# Main.net
KiCad netlist of a schematic drawn in Altium Designer
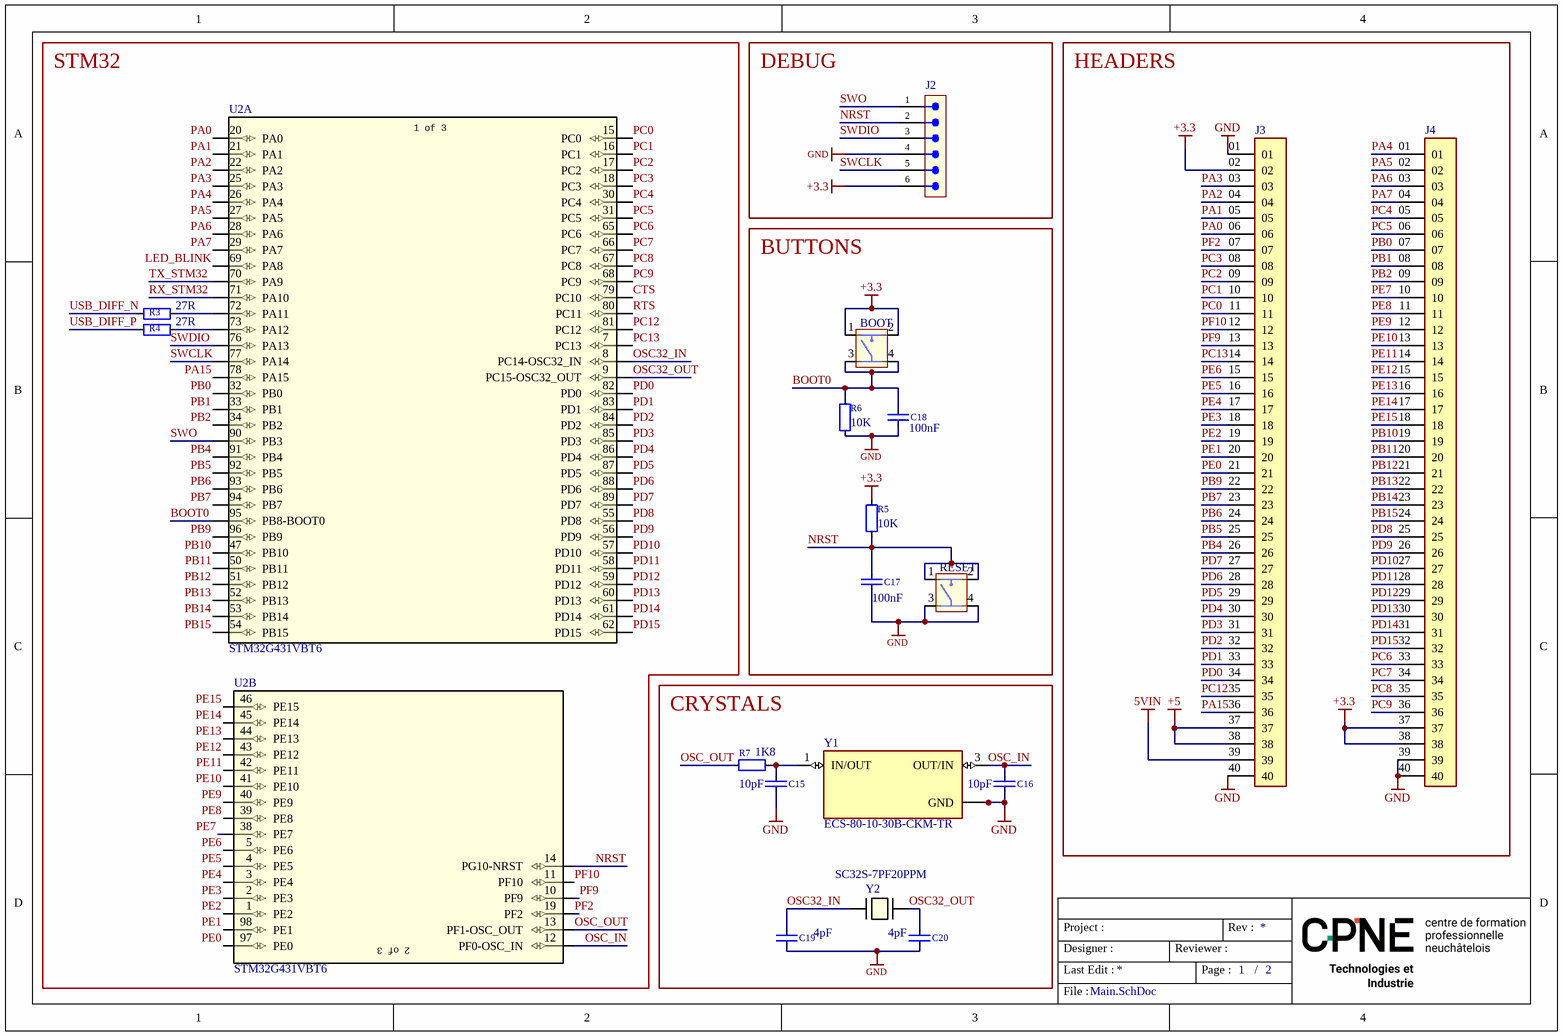
[diagram p0: Main.SchDoc]

(export (version "E")
  (design (tool "Eeschema 10.0.6"))
  (components
    (comp (ref "BOOT")
      (value "PTS645SH43SMTR92 LFS")
      (footprint "PTS645SH43SMTR92 LFS")
      (description "SWITCH TACTILE SPST-NO 0.05A 12V")
      (fields
        (field (name "MANUFACTURER") "E-Switch")
        (field (name "MANUFACTURER PART NUMBER") "TL3301NF160QG-KR")
      )
      (libsource (lib "CPNE-TI Electronic") (part "PTS645SH43SMTR92 LFS"))
    )
    (comp (ref "C15")
      (value "C_0603_10pF_50V")
      (footprint "WCAP-CSGP_0603_L1.6W0.8H0.8_Reflow")
      (description "CAP CER 10PF 50V C0G/NP0 0603 / 10 pF ±5% 50V Ceramic Capacitor C0G, NP0 0603 (1608 Metric)")
      (fields
        (field (name "MANUFACTURER PART NUMBER") "C0603C100J5GACTU")
        (field (name "DISPLAYED VALUE") "10pF")
        (field (name "MANUFACTURER") "Kemet")
      )
      (libsource (lib "CPNE-TI Electronic") (part "Capacitor_Non-Polarized"))
    )
    (comp (ref "C16")
      (value "C_0603_10pF_50V")
      (footprint "WCAP-CSGP_0603_L1.6W0.8H0.8_Reflow")
      (description "CAP CER 10PF 50V C0G/NP0 0603 / 10 pF ±5% 50V Ceramic Capacitor C0G, NP0 0603 (1608 Metric)")
      (fields
        (field (name "MANUFACTURER PART NUMBER") "C0603C100J5GACTU")
        (field (name "DISPLAYED VALUE") "10pF")
        (field (name "MANUFACTURER") "Kemet")
      )
      (libsource (lib "CPNE-TI Electronic") (part "Capacitor_Non-Polarized"))
    )
    (comp (ref "C17")
      (value "C_0805_100n0_X7R")
      (footprint "SMD_0805_footprint")
      (fields
        (field (name "MANUFACTURER PART NUMBER") "885012207098")
        (field (name "MANUFACTURER") "Würth Elektronik")
        (field (name "DISPLAYED VALUE") "100nF")
      )
      (libsource (lib "CPNE-TI Electronic") (part "Capacitor_Non-Polarized"))
    )
    (comp (ref "C18")
      (value "C_0805_100n0_X7R")
      (footprint "SMD_0805_footprint")
      (fields
        (field (name "MANUFACTURER PART NUMBER") "885012207098")
        (field (name "MANUFACTURER") "Würth Elektronik")
        (field (name "DISPLAYED VALUE") "100nF")
      )
      (libsource (lib "CPNE-TI Electronic") (part "Capacitor_Non-Polarized"))
    )
    (comp (ref "C19")
      (value "C_0603_4pF_50V")
      (footprint "WCAP-CSGP_0603_L1.6W0.8H0.8_Reflow")
      (description "CAP CER 4PF 50V C0G/NP0 0603 / 10 pF ±5% 50V Ceramic Capacitor C0G, NP0 0603 (1608 Metric)")
      (fields
        (field (name "MANUFACTURER PART NUMBER") "CC0603CRNPO9BN4R0")
        (field (name "DISPLAYED VALUE") "4pF")
        (field (name "MANUFACTURER") "Yageo")
      )
      (libsource (lib "CPNE-TI Electronic") (part "Capacitor_Non-Polarized"))
    )
    (comp (ref "C20")
      (value "C_0603_4pF_50V")
      (footprint "WCAP-CSGP_0603_L1.6W0.8H0.8_Reflow")
      (description "CAP CER 4PF 50V C0G/NP0 0603 / 10 pF ±5% 50V Ceramic Capacitor C0G, NP0 0603 (1608 Metric)")
      (fields
        (field (name "MANUFACTURER PART NUMBER") "CC0603CRNPO9BN4R0")
        (field (name "DISPLAYED VALUE") "4pF")
        (field (name "MANUFACTURER") "Yageo")
      )
      (libsource (lib "CPNE-TI Electronic") (part "Capacitor_Non-Polarized"))
    )
    (comp (ref "J2")
      (value "THT 1-Row Vertical Pin Header, 6 Pins, Pitch 2.54mm")
      (footprint "61300611121")
      (description "THT Vertical Pin Header WR-PHD, Pitch 2.54mm, Single Row, 6 Pins")
      (fields
        (field (name "MANUFACTURER") "Würth Elektronik")
        (field (name "MANUFACTURER PART NUMBER") "613 006 11121")
      )
      (libsource (lib "CPNE-TI Electronic") (part "Header_Male_1R_6P"))
    )
    (comp (ref "J3")
      (value "THT 1-Row Vertical Pin Header, 40 Pins, Pitch 2.54mm")
      (footprint "THT 1-Row Vertical Pin Header, 40 Pins, Pitch 2.54mm")
      (description "THT Vertical Pin Header WR-PHD, Pitch 2.54mm, Single Row, 40 Pins")
      (fields
        (field (name "MANUFACTURER") "Würth Elektronik")
        (field (name "MANUFACTURER PART NUMBER") "613 008 11121")
      )
      (libsource (lib "CPNE-TI Electronic") (part "Header_Male_1R_40P"))
    )
    (comp (ref "J4")
      (value "THT 1-Row Vertical Pin Header, 40 Pins, Pitch 2.54mm")
      (footprint "THT 1-Row Vertical Pin Header, 40 Pins, Pitch 2.54mm")
      (description "THT Vertical Pin Header WR-PHD, Pitch 2.54mm, Single Row, 40 Pins")
      (fields
        (field (name "MANUFACTURER") "Würth Elektronik")
        (field (name "MANUFACTURER PART NUMBER") "613 008 11121")
      )
      (libsource (lib "CPNE-TI Electronic") (part "Header_Male_1R_40P"))
    )
    (comp (ref "R3")
      (value "R_0805_27R0")
      (footprint "SMD_0805_footprint")
      (description "Res Thick Film 0805 27 Ohm 1% 0.125W ±100ppm/°C Molded SMD Punched Carrier T/R")
      (fields
        (field (name "DISPLAYED VALUE") "27R")
        (field (name "MANUFACTURER PART NUMBER") "CRCW080527R0JNTA")
        (field (name "MANUFACTURER") "Panasonic")
      )
      (libsource (lib "") (part "Resistor_Symbol_1"))
    )
    (comp (ref "R4")
      (value "R_0805_27R0")
      (footprint "SMD_0805_footprint")
      (description "Res Thick Film 0805 27 Ohm 1% 0.125W ±100ppm/°C Molded SMD Punched Carrier T/R")
      (fields
        (field (name "DISPLAYED VALUE") "27R")
        (field (name "MANUFACTURER PART NUMBER") "CRCW080527R0JNTA")
        (field (name "MANUFACTURER") "Panasonic")
      )
      (libsource (lib "") (part "Resistor_Symbol_1"))
    )
    (comp (ref "R5")
      (value "R_0805_10K_0.125W")
      (footprint "SMD_0805_footprint")
      (description "Res Thick Film 0805 10K Ohm 1% 0.125W(1/8W) ±100ppm/C Pad SMD Automotive T/R")
      (fields
        (field (name "MANUFACTURER PART NUMBER") "ERJ-6ENF1002V")
        (field (name "MANUFACTURER") "Panasonic")
        (field (name "DISPLAYED VALUE") "10K")
      )
      (libsource (lib "CPNE-TI Electronic") (part "Resistor_Symbol"))
    )
    (comp (ref "R6")
      (value "R_0805_10K_0.125W")
      (footprint "SMD_0805_footprint")
      (description "Res Thick Film 0805 10K Ohm 1% 0.125W(1/8W) ±100ppm/C Pad SMD Automotive T/R")
      (fields
        (field (name "MANUFACTURER PART NUMBER") "ERJ-6ENF1002V")
        (field (name "MANUFACTURER") "Panasonic")
        (field (name "DISPLAYED VALUE") "10K")
      )
      (libsource (lib "CPNE-TI Electronic") (part "Resistor_Symbol"))
    )
    (comp (ref "R7")
      (value "R_0805_1K80")
      (footprint "SMD_0805_footprint")
      (description "Resistor 1K8, SMD 0805, 1% 0.125W")
      (fields
        (field (name "DISPLAYED VALUE") "1K8")
        (field (name "MANUFACTURER") "Panasonic")
        (field (name "MANUFACTURER PART NUMBER") "ERJ-6ENF1801V")
      )
      (libsource (lib "") (part "Resistor_Symbol_1"))
    )
    (comp (ref "RESET")
      (value "PTS645SH43SMTR92 LFS")
      (footprint "PTS645SH43SMTR92 LFS")
      (description "SWITCH TACTILE SPST-NO 0.05A 12V")
      (fields
        (field (name "MANUFACTURER") "E-Switch")
        (field (name "MANUFACTURER PART NUMBER") "TL3301NF160QG-KR")
      )
      (libsource (lib "CPNE-TI Electronic") (part "PTS645SH43SMTR92 LFS"))
    )
    (comp (ref "U2")
      (value "STM32G431VBT6")
      (footprint "LQFP100")
      (description "Microcontroller 32-Bit ARM Cortex-M4 RISC 128KB Flash 1.71V to 3.6V 100-Pin LQFP")
      (libsource (lib "CPNE-TI Electronic") (part "STM32G431VBT6"))
    )
    (comp (ref "Y1")
      (value "ECS-80-10-30B-CKM-TR")
      (footprint "ECS-80-10-30B-CKM-TR")
      (description "Crystal, Standard, 8 MHz, SMD, 5mm x 3.2mm x 0.85mm, 10 ppm, 10 pF, 10 ppm, ECX-53B")
      (libsource (lib "CPNE-TI Electronic") (part "ECS-80-10-30B-CKM-TR"))
    )
    (comp (ref "Y2")
      (value "SC32S-7PF20PPM")
      (footprint "SC32S-7PF20PPM-Footprint-1")
      (description "Crystal 0.032768MHz ±20ppm (Tol) 7pF FUND 70000Ohm 2-Pin SMD T/R")
      (libsource (lib "CPNE-TI Electronic") (part "SC32S-7PF20PPM-Symbol-1"))
    )
  )
  (nets
    (net (code "1") (name "+3.3") (class "Default")
      (node (ref "BOOT") (pin "1") (pinfunction "1_1") (pintype "passive"))
      (node (ref "BOOT") (pin "2") (pinfunction "2_2") (pintype "passive"))
      (node (ref "J2") (pin "6") (pinfunction "6_6") (pintype "passive"))
      (node (ref "J3") (pin "02") (pinfunction "02_02") (pintype "passive"))
      (node (ref "J4") (pin "37") (pinfunction "37_37") (pintype "passive"))
      (node (ref "J4") (pin "38") (pinfunction "38_38") (pintype "passive"))
      (node (ref "R5") (pin "2") (pinfunction "2_2") (pintype "passive"))
    )
    (net (code "2") (name "+5") (class "Default")
      (node (ref "J3") (pin "37") (pinfunction "37_37") (pintype "passive"))
      (node (ref "J3") (pin "38") (pinfunction "38_38") (pintype "passive"))
    )
    (net (code "3") (name "/BOOT0") (class "Default")
      (node (ref "BOOT") (pin "3") (pinfunction "3_3") (pintype "passive"))
      (node (ref "BOOT") (pin "4") (pinfunction "4_4") (pintype "passive"))
      (node (ref "C18") (pin "2") (pinfunction "2_2") (pintype "passive"))
      (node (ref "R6") (pin "2") (pinfunction "2_2") (pintype "passive"))
      (node (ref "U2") (pin "95") (pinfunction "PB8-BOOT0_95") (pintype "bidirectional"))
    )
    (net (code "4") (name "/CTS") (class "Default")
      (node (ref "U2") (pin "79") (pinfunction "PC10_79") (pintype "bidirectional"))
    )
    (net (code "5") (name "/LED_BLINK") (class "Default")
      (node (ref "U2") (pin "69") (pinfunction "PA8_69") (pintype "bidirectional"))
    )
    (net (code "6") (name "/NRST") (class "Default")
      (node (ref "C17") (pin "2") (pinfunction "2_2") (pintype "passive"))
      (node (ref "J2") (pin "2") (pinfunction "2_2") (pintype "passive"))
      (node (ref "R5") (pin "1") (pinfunction "1_1") (pintype "passive"))
      (node (ref "RESET") (pin "1") (pinfunction "1_1") (pintype "passive"))
      (node (ref "RESET") (pin "2") (pinfunction "2_2") (pintype "passive"))
      (node (ref "U2") (pin "14") (pinfunction "PG10-NRST_14") (pintype "bidirectional"))
    )
    (net (code "7") (name "/OSC32_IN") (class "Default")
      (node (ref "C19") (pin "2") (pinfunction "2_2") (pintype "passive"))
      (node (ref "U2") (pin "8") (pinfunction "PC14-OSC32_IN_8") (pintype "bidirectional"))
      (node (ref "Y2") (pin "1") (pinfunction "1_1") (pintype "passive"))
    )
    (net (code "8") (name "/OSC32_OUT") (class "Default")
      (node (ref "C20") (pin "2") (pinfunction "2_2") (pintype "passive"))
      (node (ref "U2") (pin "9") (pinfunction "PC15-OSC32_OUT_9") (pintype "bidirectional"))
      (node (ref "Y2") (pin "2") (pinfunction "2_2") (pintype "passive"))
    )
    (net (code "9") (name "/OSC_IN") (class "Default")
      (node (ref "C16") (pin "2") (pinfunction "2_2") (pintype "passive"))
      (node (ref "U2") (pin "12") (pinfunction "PF0-OSC_IN_12") (pintype "bidirectional"))
      (node (ref "Y1") (pin "3") (pinfunction "OUT/IN_3") (pintype "bidirectional"))
    )
    (net (code "10") (name "/OSC_OUT") (class "Default")
      (node (ref "R7") (pin "1") (pinfunction "1_1") (pintype "passive"))
      (node (ref "U2") (pin "13") (pinfunction "PF1-OSC_OUT_13") (pintype "bidirectional"))
    )
    (net (code "11") (name "/PA0") (class "Default")
      (node (ref "J3") (pin "06") (pinfunction "06_06") (pintype "passive"))
      (node (ref "U2") (pin "20") (pinfunction "PA0_20") (pintype "bidirectional"))
    )
    (net (code "12") (name "/PA1") (class "Default")
      (node (ref "J3") (pin "05") (pinfunction "05_05") (pintype "passive"))
      (node (ref "U2") (pin "21") (pinfunction "PA1_21") (pintype "bidirectional"))
    )
    (net (code "13") (name "/PA2") (class "Default")
      (node (ref "J3") (pin "04") (pinfunction "04_04") (pintype "passive"))
      (node (ref "U2") (pin "22") (pinfunction "PA2_22") (pintype "bidirectional"))
    )
    (net (code "14") (name "/PA3") (class "Default")
      (node (ref "J3") (pin "03") (pinfunction "03_03") (pintype "passive"))
      (node (ref "U2") (pin "25") (pinfunction "PA3_25") (pintype "bidirectional"))
    )
    (net (code "15") (name "/PA4") (class "Default")
      (node (ref "J4") (pin "01") (pinfunction "01_01") (pintype "passive"))
      (node (ref "U2") (pin "26") (pinfunction "PA4_26") (pintype "bidirectional"))
    )
    (net (code "16") (name "/PA5") (class "Default")
      (node (ref "J4") (pin "02") (pinfunction "02_02") (pintype "passive"))
      (node (ref "U2") (pin "27") (pinfunction "PA5_27") (pintype "bidirectional"))
    )
    (net (code "17") (name "/PA6") (class "Default")
      (node (ref "J4") (pin "03") (pinfunction "03_03") (pintype "passive"))
      (node (ref "U2") (pin "28") (pinfunction "PA6_28") (pintype "bidirectional"))
    )
    (net (code "18") (name "/PA7") (class "Default")
      (node (ref "J4") (pin "04") (pinfunction "04_04") (pintype "passive"))
      (node (ref "U2") (pin "29") (pinfunction "PA7_29") (pintype "bidirectional"))
    )
    (net (code "19") (name "/PA15") (class "Default")
      (node (ref "J3") (pin "36") (pinfunction "36_36") (pintype "passive"))
      (node (ref "U2") (pin "78") (pinfunction "PA15_78") (pintype "bidirectional"))
    )
    (net (code "20") (name "/PB0") (class "Default")
      (node (ref "J4") (pin "07") (pinfunction "07_07") (pintype "passive"))
      (node (ref "U2") (pin "32") (pinfunction "PB0_32") (pintype "bidirectional"))
    )
    (net (code "21") (name "/PB1") (class "Default")
      (node (ref "J4") (pin "08") (pinfunction "08_08") (pintype "passive"))
      (node (ref "U2") (pin "33") (pinfunction "PB1_33") (pintype "bidirectional"))
    )
    (net (code "22") (name "/PB2") (class "Default")
      (node (ref "J4") (pin "09") (pinfunction "09_09") (pintype "passive"))
      (node (ref "U2") (pin "34") (pinfunction "PB2_34") (pintype "bidirectional"))
    )
    (net (code "23") (name "/PB4") (class "Default")
      (node (ref "J3") (pin "26") (pinfunction "26_26") (pintype "passive"))
      (node (ref "U2") (pin "91") (pinfunction "PB4_91") (pintype "bidirectional"))
    )
    (net (code "24") (name "/PB5") (class "Default")
      (node (ref "J3") (pin "25") (pinfunction "25_25") (pintype "passive"))
      (node (ref "U2") (pin "92") (pinfunction "PB5_92") (pintype "bidirectional"))
    )
    (net (code "25") (name "/PB6") (class "Default")
      (node (ref "J3") (pin "24") (pinfunction "24_24") (pintype "passive"))
      (node (ref "U2") (pin "93") (pinfunction "PB6_93") (pintype "bidirectional"))
    )
    (net (code "26") (name "/PB7") (class "Default")
      (node (ref "J3") (pin "23") (pinfunction "23_23") (pintype "passive"))
      (node (ref "U2") (pin "94") (pinfunction "PB7_94") (pintype "bidirectional"))
    )
    (net (code "27") (name "/PB9") (class "Default")
      (node (ref "J3") (pin "22") (pinfunction "22_22") (pintype "passive"))
      (node (ref "U2") (pin "96") (pinfunction "PB9_96") (pintype "bidirectional"))
    )
    (net (code "28") (name "/PB10") (class "Default")
      (node (ref "J4") (pin "19") (pinfunction "19_19") (pintype "passive"))
      (node (ref "U2") (pin "47") (pinfunction "PB10_47") (pintype "bidirectional"))
    )
    (net (code "29") (name "/PB11") (class "Default")
      (node (ref "J4") (pin "20") (pinfunction "20_20") (pintype "passive"))
      (node (ref "U2") (pin "50") (pinfunction "PB11_50") (pintype "bidirectional"))
    )
    (net (code "30") (name "/PB12") (class "Default")
      (node (ref "J4") (pin "21") (pinfunction "21_21") (pintype "passive"))
      (node (ref "U2") (pin "51") (pinfunction "PB12_51") (pintype "bidirectional"))
    )
    (net (code "31") (name "/PB13") (class "Default")
      (node (ref "J4") (pin "22") (pinfunction "22_22") (pintype "passive"))
      (node (ref "U2") (pin "52") (pinfunction "PB13_52") (pintype "bidirectional"))
    )
    (net (code "32") (name "/PB14") (class "Default")
      (node (ref "J4") (pin "23") (pinfunction "23_23") (pintype "passive"))
      (node (ref "U2") (pin "53") (pinfunction "PB14_53") (pintype "bidirectional"))
    )
    (net (code "33") (name "/PB15") (class "Default")
      (node (ref "J4") (pin "24") (pinfunction "24_24") (pintype "passive"))
      (node (ref "U2") (pin "54") (pinfunction "PB15_54") (pintype "bidirectional"))
    )
    (net (code "34") (name "/PC0") (class "Default")
      (node (ref "J3") (pin "11") (pinfunction "11_11") (pintype "passive"))
      (node (ref "U2") (pin "15") (pinfunction "PC0_15") (pintype "bidirectional"))
    )
    (net (code "35") (name "/PC1") (class "Default")
      (node (ref "J3") (pin "10") (pinfunction "10_10") (pintype "passive"))
      (node (ref "U2") (pin "16") (pinfunction "PC1_16") (pintype "bidirectional"))
    )
    (net (code "36") (name "/PC2") (class "Default")
      (node (ref "J3") (pin "09") (pinfunction "09_09") (pintype "passive"))
      (node (ref "U2") (pin "17") (pinfunction "PC2_17") (pintype "bidirectional"))
    )
    (net (code "37") (name "/PC3") (class "Default")
      (node (ref "J3") (pin "08") (pinfunction "08_08") (pintype "passive"))
      (node (ref "U2") (pin "18") (pinfunction "PC3_18") (pintype "bidirectional"))
    )
    (net (code "38") (name "/PC4") (class "Default")
      (node (ref "J4") (pin "05") (pinfunction "05_05") (pintype "passive"))
      (node (ref "U2") (pin "30") (pinfunction "PC4_30") (pintype "bidirectional"))
    )
    (net (code "39") (name "/PC5") (class "Default")
      (node (ref "J4") (pin "06") (pinfunction "06_06") (pintype "passive"))
      (node (ref "U2") (pin "31") (pinfunction "PC5_31") (pintype "bidirectional"))
    )
    (net (code "40") (name "/PC6") (class "Default")
      (node (ref "J4") (pin "33") (pinfunction "33_33") (pintype "passive"))
      (node (ref "U2") (pin "65") (pinfunction "PC6_65") (pintype "bidirectional"))
    )
    (net (code "41") (name "/PC7") (class "Default")
      (node (ref "J4") (pin "34") (pinfunction "34_34") (pintype "passive"))
      (node (ref "U2") (pin "66") (pinfunction "PC7_66") (pintype "bidirectional"))
    )
    (net (code "42") (name "/PC8") (class "Default")
      (node (ref "J4") (pin "35") (pinfunction "35_35") (pintype "passive"))
      (node (ref "U2") (pin "67") (pinfunction "PC8_67") (pintype "bidirectional"))
    )
    (net (code "43") (name "/PC9") (class "Default")
      (node (ref "J4") (pin "36") (pinfunction "36_36") (pintype "passive"))
      (node (ref "U2") (pin "68") (pinfunction "PC9_68") (pintype "bidirectional"))
    )
    (net (code "44") (name "/PC12") (class "Default")
      (node (ref "J3") (pin "35") (pinfunction "35_35") (pintype "passive"))
      (node (ref "U2") (pin "81") (pinfunction "PC12_81") (pintype "bidirectional"))
    )
    (net (code "45") (name "/PC13") (class "Default")
      (node (ref "J3") (pin "14") (pinfunction "14_14") (pintype "passive"))
      (node (ref "U2") (pin "7") (pinfunction "PC13_7") (pintype "bidirectional"))
    )
    (net (code "46") (name "/PD0") (class "Default")
      (node (ref "J3") (pin "34") (pinfunction "34_34") (pintype "passive"))
      (node (ref "U2") (pin "82") (pinfunction "PD0_82") (pintype "bidirectional"))
    )
    (net (code "47") (name "/PD1") (class "Default")
      (node (ref "J3") (pin "33") (pinfunction "33_33") (pintype "passive"))
      (node (ref "U2") (pin "83") (pinfunction "PD1_83") (pintype "bidirectional"))
    )
    (net (code "48") (name "/PD2") (class "Default")
      (node (ref "J3") (pin "32") (pinfunction "32_32") (pintype "passive"))
      (node (ref "U2") (pin "84") (pinfunction "PD2_84") (pintype "bidirectional"))
    )
    (net (code "49") (name "/PD3") (class "Default")
      (node (ref "J3") (pin "31") (pinfunction "31_31") (pintype "passive"))
      (node (ref "U2") (pin "85") (pinfunction "PD3_85") (pintype "bidirectional"))
    )
    (net (code "50") (name "/PD4") (class "Default")
      (node (ref "J3") (pin "30") (pinfunction "30_30") (pintype "passive"))
      (node (ref "U2") (pin "86") (pinfunction "PD4_86") (pintype "bidirectional"))
    )
    (net (code "51") (name "/PD5") (class "Default")
      (node (ref "J3") (pin "29") (pinfunction "29_29") (pintype "passive"))
      (node (ref "U2") (pin "87") (pinfunction "PD5_87") (pintype "bidirectional"))
    )
    (net (code "52") (name "/PD6") (class "Default")
      (node (ref "J3") (pin "28") (pinfunction "28_28") (pintype "passive"))
      (node (ref "U2") (pin "88") (pinfunction "PD6_88") (pintype "bidirectional"))
    )
    (net (code "53") (name "/PD7") (class "Default")
      (node (ref "J3") (pin "27") (pinfunction "27_27") (pintype "passive"))
      (node (ref "U2") (pin "89") (pinfunction "PD7_89") (pintype "bidirectional"))
    )
    (net (code "54") (name "/PD8") (class "Default")
      (node (ref "J4") (pin "25") (pinfunction "25_25") (pintype "passive"))
      (node (ref "U2") (pin "55") (pinfunction "PD8_55") (pintype "bidirectional"))
    )
    (net (code "55") (name "/PD9") (class "Default")
      (node (ref "J4") (pin "26") (pinfunction "26_26") (pintype "passive"))
      (node (ref "U2") (pin "56") (pinfunction "PD9_56") (pintype "bidirectional"))
    )
    (net (code "56") (name "/PD10") (class "Default")
      (node (ref "J4") (pin "27") (pinfunction "27_27") (pintype "passive"))
      (node (ref "U2") (pin "57") (pinfunction "PD10_57") (pintype "bidirectional"))
    )
    (net (code "57") (name "/PD11") (class "Default")
      (node (ref "J4") (pin "28") (pinfunction "28_28") (pintype "passive"))
      (node (ref "U2") (pin "58") (pinfunction "PD11_58") (pintype "bidirectional"))
    )
    (net (code "58") (name "/PD12") (class "Default")
      (node (ref "J4") (pin "29") (pinfunction "29_29") (pintype "passive"))
      (node (ref "U2") (pin "59") (pinfunction "PD12_59") (pintype "bidirectional"))
    )
    (net (code "59") (name "/PD13") (class "Default")
      (node (ref "J4") (pin "30") (pinfunction "30_30") (pintype "passive"))
      (node (ref "U2") (pin "60") (pinfunction "PD13_60") (pintype "bidirectional"))
    )
    (net (code "60") (name "/PD14") (class "Default")
      (node (ref "J4") (pin "31") (pinfunction "31_31") (pintype "passive"))
      (node (ref "U2") (pin "61") (pinfunction "PD14_61") (pintype "bidirectional"))
    )
    (net (code "61") (name "/PD15") (class "Default")
      (node (ref "J4") (pin "32") (pinfunction "32_32") (pintype "passive"))
      (node (ref "U2") (pin "62") (pinfunction "PD15_62") (pintype "bidirectional"))
    )
    (net (code "62") (name "/PE0") (class "Default")
      (node (ref "J3") (pin "21") (pinfunction "21_21") (pintype "passive"))
      (node (ref "U2") (pin "97") (pinfunction "PE0_97") (pintype "bidirectional"))
    )
    (net (code "63") (name "/PE1") (class "Default")
      (node (ref "J3") (pin "20") (pinfunction "20_20") (pintype "passive"))
      (node (ref "U2") (pin "98") (pinfunction "PE1_98") (pintype "bidirectional"))
    )
    (net (code "64") (name "/PE2") (class "Default")
      (node (ref "J3") (pin "19") (pinfunction "19_19") (pintype "passive"))
      (node (ref "U2") (pin "1") (pinfunction "PE2_1") (pintype "bidirectional"))
    )
    (net (code "65") (name "/PE3") (class "Default")
      (node (ref "J3") (pin "18") (pinfunction "18_18") (pintype "passive"))
      (node (ref "U2") (pin "2") (pinfunction "PE3_2") (pintype "bidirectional"))
    )
    (net (code "66") (name "/PE4") (class "Default")
      (node (ref "J3") (pin "17") (pinfunction "17_17") (pintype "passive"))
      (node (ref "U2") (pin "3") (pinfunction "PE4_3") (pintype "bidirectional"))
    )
    (net (code "67") (name "/PE5") (class "Default")
      (node (ref "J3") (pin "16") (pinfunction "16_16") (pintype "passive"))
      (node (ref "U2") (pin "4") (pinfunction "PE5_4") (pintype "bidirectional"))
    )
    (net (code "68") (name "/PE6") (class "Default")
      (node (ref "J3") (pin "15") (pinfunction "15_15") (pintype "passive"))
      (node (ref "U2") (pin "5") (pinfunction "PE6_5") (pintype "bidirectional"))
    )
    (net (code "69") (name "/PE7") (class "Default")
      (node (ref "J4") (pin "10") (pinfunction "10_10") (pintype "passive"))
      (node (ref "U2") (pin "38") (pinfunction "PE7_38") (pintype "bidirectional"))
    )
    (net (code "70") (name "/PE8") (class "Default")
      (node (ref "J4") (pin "11") (pinfunction "11_11") (pintype "passive"))
      (node (ref "U2") (pin "39") (pinfunction "PE8_39") (pintype "bidirectional"))
    )
    (net (code "71") (name "/PE9") (class "Default")
      (node (ref "J4") (pin "12") (pinfunction "12_12") (pintype "passive"))
      (node (ref "U2") (pin "40") (pinfunction "PE9_40") (pintype "bidirectional"))
    )
    (net (code "72") (name "/PE10") (class "Default")
      (node (ref "J4") (pin "13") (pinfunction "13_13") (pintype "passive"))
      (node (ref "U2") (pin "41") (pinfunction "PE10_41") (pintype "bidirectional"))
    )
    (net (code "73") (name "/PE11") (class "Default")
      (node (ref "J4") (pin "14") (pinfunction "14_14") (pintype "passive"))
      (node (ref "U2") (pin "42") (pinfunction "PE11_42") (pintype "bidirectional"))
    )
    (net (code "74") (name "/PE12") (class "Default")
      (node (ref "J4") (pin "15") (pinfunction "15_15") (pintype "passive"))
      (node (ref "U2") (pin "43") (pinfunction "PE12_43") (pintype "bidirectional"))
    )
    (net (code "75") (name "/PE13") (class "Default")
      (node (ref "J4") (pin "16") (pinfunction "16_16") (pintype "passive"))
      (node (ref "U2") (pin "44") (pinfunction "PE13_44") (pintype "bidirectional"))
    )
    (net (code "76") (name "/PE14") (class "Default")
      (node (ref "J4") (pin "17") (pinfunction "17_17") (pintype "passive"))
      (node (ref "U2") (pin "45") (pinfunction "PE14_45") (pintype "bidirectional"))
    )
    (net (code "77") (name "/PE15") (class "Default")
      (node (ref "J4") (pin "18") (pinfunction "18_18") (pintype "passive"))
      (node (ref "U2") (pin "46") (pinfunction "PE15_46") (pintype "bidirectional"))
    )
    (net (code "78") (name "/PF2") (class "Default")
      (node (ref "J3") (pin "07") (pinfunction "07_07") (pintype "passive"))
      (node (ref "U2") (pin "19") (pinfunction "PF2_19") (pintype "bidirectional"))
    )
    (net (code "79") (name "/PF9") (class "Default")
      (node (ref "J3") (pin "13") (pinfunction "13_13") (pintype "passive"))
      (node (ref "U2") (pin "10") (pinfunction "PF9_10") (pintype "bidirectional"))
    )
    (net (code "80") (name "/PF10") (class "Default")
      (node (ref "J3") (pin "12") (pinfunction "12_12") (pintype "passive"))
      (node (ref "U2") (pin "11") (pinfunction "PF10_11") (pintype "bidirectional"))
    )
    (net (code "81") (name "/RTS") (class "Default")
      (node (ref "U2") (pin "80") (pinfunction "PC11_80") (pintype "bidirectional"))
    )
    (net (code "82") (name "/RX_STM32") (class "Default")
      (node (ref "U2") (pin "71") (pinfunction "PA10_71") (pintype "bidirectional"))
    )
    (net (code "83") (name "/SWCLK") (class "Default")
      (node (ref "J2") (pin "5") (pinfunction "5_5") (pintype "passive"))
      (node (ref "U2") (pin "77") (pinfunction "PA14_77") (pintype "bidirectional"))
    )
    (net (code "84") (name "/SWDIO") (class "Default")
      (node (ref "J2") (pin "3") (pinfunction "3_3") (pintype "passive"))
      (node (ref "U2") (pin "76") (pinfunction "PA13_76") (pintype "bidirectional"))
    )
    (net (code "85") (name "/SWO") (class "Default")
      (node (ref "J2") (pin "1") (pinfunction "1_1") (pintype "passive"))
      (node (ref "U2") (pin "90") (pinfunction "PB3_90") (pintype "bidirectional"))
    )
    (net (code "86") (name "/TX_STM32") (class "Default")
      (node (ref "U2") (pin "70") (pinfunction "PA9_70") (pintype "bidirectional"))
    )
    (net (code "87") (name "/USB_DIFF_N") (class "Default")
      (node (ref "R3") (pin "1") (pinfunction "1_1") (pintype "passive"))
    )
    (net (code "88") (name "/USB_DIFF_P") (class "Default")
      (node (ref "R4") (pin "1") (pinfunction "1_1") (pintype "passive"))
    )
    (net (code "89") (name "5VIN") (class "Default")
      (node (ref "J3") (pin "39") (pinfunction "39_39") (pintype "passive"))
    )
    (net (code "90") (name "GND") (class "Default")
      (node (ref "C15") (pin "1") (pinfunction "1_1") (pintype "passive"))
      (node (ref "C16") (pin "1") (pinfunction "1_1") (pintype "passive"))
      (node (ref "C17") (pin "1") (pinfunction "1_1") (pintype "passive"))
      (node (ref "C18") (pin "1") (pinfunction "1_1") (pintype "passive"))
      (node (ref "C19") (pin "1") (pinfunction "1_1") (pintype "passive"))
      (node (ref "C20") (pin "1") (pinfunction "1_1") (pintype "passive"))
      (node (ref "J2") (pin "4") (pinfunction "4_4") (pintype "passive"))
      (node (ref "J3") (pin "01") (pinfunction "01_01") (pintype "passive"))
      (node (ref "J3") (pin "40") (pinfunction "40_40") (pintype "passive"))
      (node (ref "J4") (pin "39") (pinfunction "39_39") (pintype "passive"))
      (node (ref "J4") (pin "40") (pinfunction "40_40") (pintype "passive"))
      (node (ref "R6") (pin "1") (pinfunction "1_1") (pintype "passive"))
      (node (ref "RESET") (pin "3") (pinfunction "3_3") (pintype "passive"))
      (node (ref "RESET") (pin "4") (pinfunction "4_4") (pintype "passive"))
      (node (ref "Y1") (pin "2") (pinfunction "GND_2") (pintype "power_in"))
      (node (ref "Y1") (pin "4") (pinfunction "GND_4") (pintype "power_in"))
    )
    (net (code "91") (name "Net-(U2A-PA11)") (class "Default")
      (node (ref "R3") (pin "2") (pinfunction "2_2") (pintype "passive"))
      (node (ref "U2") (pin "72") (pinfunction "PA11_72") (pintype "bidirectional"))
    )
    (net (code "92") (name "Net-(U2A-PA12)") (class "Default")
      (node (ref "R4") (pin "2") (pinfunction "2_2") (pintype "passive"))
      (node (ref "U2") (pin "73") (pinfunction "PA12_73") (pintype "bidirectional"))
    )
    (net (code "93") (name "Net-(Y1-IN{slash}OUT)") (class "Default")
      (node (ref "C15") (pin "2") (pinfunction "2_2") (pintype "passive"))
      (node (ref "R7") (pin "2") (pinfunction "2_2") (pintype "passive"))
      (node (ref "Y1") (pin "1") (pinfunction "IN/OUT_1") (pintype "bidirectional"))
    )
  )
)
